# BrHalf.net
KiCad netlist of a schematic drawn in EAGLE
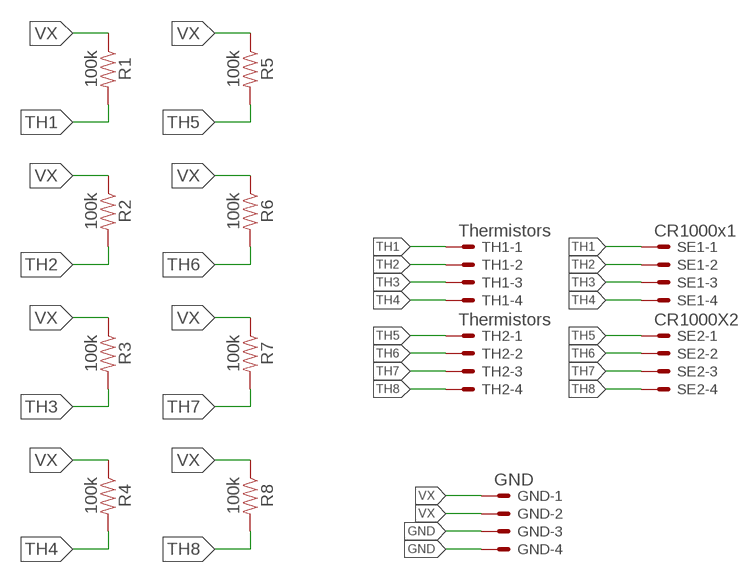
[diagram p0: schematic, sheet 1]

(export (version "E")
  (design (tool "Eeschema 10.0.6"))
  (components
    (comp (ref "GND")
      (value "GND")
      (footprint "eagle-import:22-23-2041")
      (fields (field (name "MF") "MOLEX") (field (name "MPN") "22-23-2041"))
      (libsource (lib "eagle-import") (part "22-23-2041"))
    )
    (comp (ref "R1")
      (value "100k")
      (footprint "eagle-import:AXIAL-0.3")
      (libsource (lib "eagle-import") (part "100KOHM-HORIZ-1/4W-5%"))
    )
    (comp (ref "R2")
      (value "100k")
      (footprint "eagle-import:AXIAL-0.3")
      (libsource (lib "eagle-import") (part "100KOHM-HORIZ-1/4W-5%"))
    )
    (comp (ref "R3")
      (value "100k")
      (footprint "eagle-import:AXIAL-0.3")
      (libsource (lib "eagle-import") (part "100KOHM-HORIZ-1/4W-5%"))
    )
    (comp (ref "R4")
      (value "100k")
      (footprint "eagle-import:AXIAL-0.3")
      (libsource (lib "eagle-import") (part "100KOHM-HORIZ-1/4W-5%"))
    )
    (comp (ref "R5")
      (value "100k")
      (footprint "eagle-import:AXIAL-0.3")
      (libsource (lib "eagle-import") (part "100KOHM-HORIZ-1/4W-5%"))
    )
    (comp (ref "R6")
      (value "100k")
      (footprint "eagle-import:AXIAL-0.3")
      (libsource (lib "eagle-import") (part "100KOHM-HORIZ-1/4W-5%"))
    )
    (comp (ref "R7")
      (value "100k")
      (footprint "eagle-import:AXIAL-0.3")
      (libsource (lib "eagle-import") (part "100KOHM-HORIZ-1/4W-5%"))
    )
    (comp (ref "R8")
      (value "100k")
      (footprint "eagle-import:AXIAL-0.3")
      (libsource (lib "eagle-import") (part "100KOHM-HORIZ-1/4W-5%"))
    )
    (comp (ref "SE1")
      (value "CR1000x1")
      (footprint "eagle-import:22-23-2041")
      (fields (field (name "MF") "MOLEX") (field (name "MPN") "22-23-2041"))
      (libsource (lib "eagle-import") (part "22-23-2041"))
    )
    (comp (ref "SE2")
      (value "CR1000X2")
      (footprint "eagle-import:22-23-2041")
      (fields (field (name "MF") "MOLEX") (field (name "MPN") "22-23-2041"))
      (libsource (lib "eagle-import") (part "22-23-2041"))
    )
    (comp (ref "TH1")
      (value "Thermistors")
      (footprint "eagle-import:22-23-2041")
      (fields (field (name "MF") "MOLEX") (field (name "MPN") "22-23-2041"))
      (libsource (lib "eagle-import") (part "22-23-2041"))
    )
    (comp (ref "TH2")
      (value "Thermistors")
      (footprint "eagle-import:22-23-2041")
      (fields (field (name "MF") "MOLEX") (field (name "MPN") "22-23-2041"))
      (libsource (lib "eagle-import") (part "22-23-2041"))
    )
  )
  (nets
    (net (code "1") (name "GND") (class "Default")
      (node (ref "GND") (pin "3") (pinfunction "S_3") (pintype "passive"))
      (node (ref "GND") (pin "4") (pinfunction "S_4") (pintype "passive"))
    )
    (net (code "2") (name "TH1") (class "Default")
      (node (ref "R1") (pin "P$2") (pinfunction "2_P$2") (pintype "passive"))
      (node (ref "SE1") (pin "1") (pinfunction "S_1") (pintype "passive"))
      (node (ref "TH1") (pin "1") (pinfunction "S_1") (pintype "passive"))
    )
    (net (code "3") (name "TH2") (class "Default")
      (node (ref "R2") (pin "P$2") (pinfunction "2_P$2") (pintype "passive"))
      (node (ref "SE1") (pin "2") (pinfunction "S_2") (pintype "passive"))
      (node (ref "TH1") (pin "2") (pinfunction "S_2") (pintype "passive"))
    )
    (net (code "4") (name "TH3") (class "Default")
      (node (ref "R3") (pin "P$2") (pinfunction "2_P$2") (pintype "passive"))
      (node (ref "SE1") (pin "3") (pinfunction "S_3") (pintype "passive"))
      (node (ref "TH1") (pin "3") (pinfunction "S_3") (pintype "passive"))
    )
    (net (code "5") (name "TH4") (class "Default")
      (node (ref "R4") (pin "P$2") (pinfunction "2_P$2") (pintype "passive"))
      (node (ref "SE1") (pin "4") (pinfunction "S_4") (pintype "passive"))
      (node (ref "TH1") (pin "4") (pinfunction "S_4") (pintype "passive"))
    )
    (net (code "6") (name "TH5") (class "Default")
      (node (ref "R5") (pin "P$2") (pinfunction "2_P$2") (pintype "passive"))
      (node (ref "SE2") (pin "1") (pinfunction "S_1") (pintype "passive"))
      (node (ref "TH2") (pin "1") (pinfunction "S_1") (pintype "passive"))
    )
    (net (code "7") (name "TH6") (class "Default")
      (node (ref "R6") (pin "P$2") (pinfunction "2_P$2") (pintype "passive"))
      (node (ref "SE2") (pin "2") (pinfunction "S_2") (pintype "passive"))
      (node (ref "TH2") (pin "2") (pinfunction "S_2") (pintype "passive"))
    )
    (net (code "8") (name "TH7") (class "Default")
      (node (ref "R7") (pin "P$2") (pinfunction "2_P$2") (pintype "passive"))
      (node (ref "SE2") (pin "3") (pinfunction "S_3") (pintype "passive"))
      (node (ref "TH2") (pin "3") (pinfunction "S_3") (pintype "passive"))
    )
    (net (code "9") (name "TH8") (class "Default")
      (node (ref "R8") (pin "P$2") (pinfunction "2_P$2") (pintype "passive"))
      (node (ref "SE2") (pin "4") (pinfunction "S_4") (pintype "passive"))
      (node (ref "TH2") (pin "4") (pinfunction "S_4") (pintype "passive"))
    )
    (net (code "10") (name "VX") (class "Default")
      (node (ref "GND") (pin "1") (pinfunction "S_1") (pintype "passive"))
      (node (ref "GND") (pin "2") (pinfunction "S_2") (pintype "passive"))
      (node (ref "R1") (pin "P$1") (pinfunction "1_P$1") (pintype "passive"))
      (node (ref "R2") (pin "P$1") (pinfunction "1_P$1") (pintype "passive"))
      (node (ref "R3") (pin "P$1") (pinfunction "1_P$1") (pintype "passive"))
      (node (ref "R4") (pin "P$1") (pinfunction "1_P$1") (pintype "passive"))
      (node (ref "R5") (pin "P$1") (pinfunction "1_P$1") (pintype "passive"))
      (node (ref "R6") (pin "P$1") (pinfunction "1_P$1") (pintype "passive"))
      (node (ref "R7") (pin "P$1") (pinfunction "1_P$1") (pintype "passive"))
      (node (ref "R8") (pin "P$1") (pinfunction "1_P$1") (pintype "passive"))
    )
  )
)
